# design.net
KiCad netlist of a schematic drawn in Altium Designer
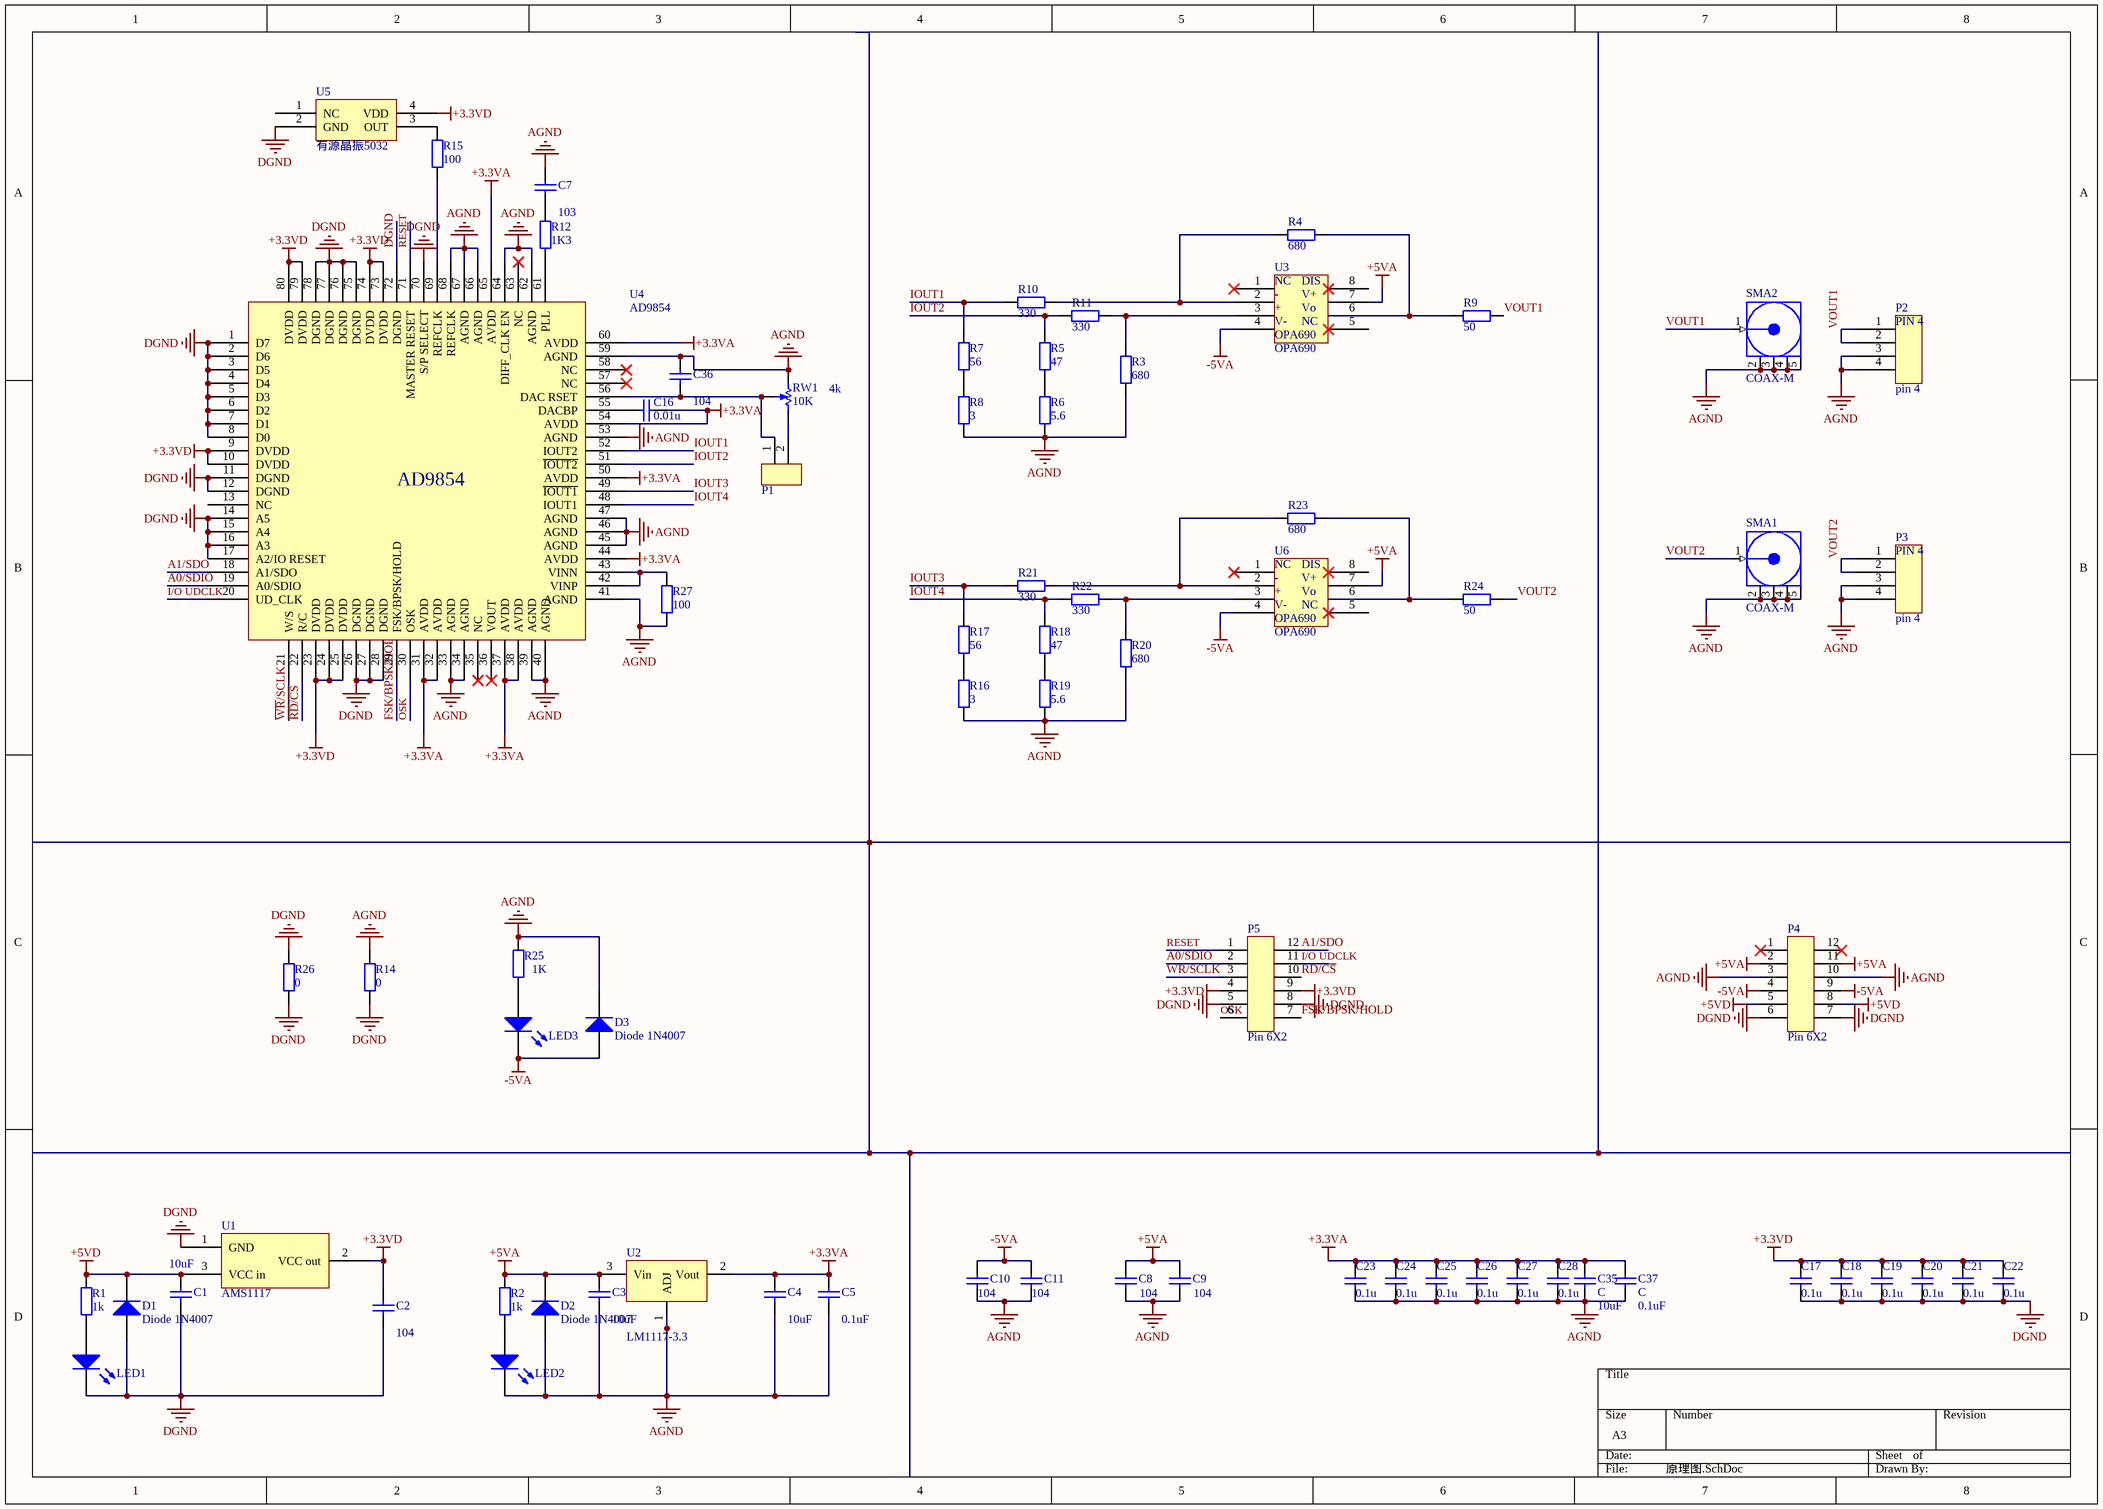
[diagram p0: 原理图.SchDoc]

(export (version "E")
  (design (tool "Eeschema 10.0.6"))
  (components
    (comp (ref "C1")
      (value "10uF")
      (footprint "0805")
      (fields (field (name "Comment") "C"))
      (libsource (lib "我的元件库") (part "C"))
    )
    (comp (ref "C2")
      (value "104")
      (footprint "0805")
      (fields (field (name "Comment") "C"))
      (libsource (lib "我的元件库") (part "C"))
    )
    (comp (ref "C3")
      (value "10uF")
      (footprint "0805")
      (fields (field (name "Comment") "C"))
      (libsource (lib "我的元件库") (part "C"))
    )
    (comp (ref "C4")
      (value "10uF")
      (footprint "0805")
      (fields (field (name "Comment") "C"))
      (libsource (lib "我的元件库") (part "C"))
    )
    (comp (ref "C5")
      (value "0.1uF")
      (footprint "0805")
      (fields (field (name "Comment") "C"))
      (libsource (lib "我的元件库") (part "C"))
    )
    (comp (ref "C7")
      (value "103")
      (footprint "0805")
      (fields (field (name "Comment") "C"))
      (libsource (lib "我的元件库") (part "C"))
    )
    (comp (ref "C8")
      (value "104")
      (footprint "0805")
      (fields (field (name "Comment") "C"))
      (libsource (lib "我的元件库") (part "C"))
    )
    (comp (ref "C9")
      (value "104")
      (footprint "0805")
      (fields (field (name "Comment") "C"))
      (libsource (lib "我的元件库") (part "C"))
    )
    (comp (ref "C10")
      (value "104")
      (footprint "0805")
      (fields (field (name "Comment") "C"))
      (libsource (lib "我的元件库") (part "C"))
    )
    (comp (ref "C11")
      (value "104")
      (footprint "0805")
      (fields (field (name "Comment") "C"))
      (libsource (lib "我的元件库") (part "C"))
    )
    (comp (ref "C16") (value "0.01u") (footprint "0805") (libsource (lib "顶层SMD") (part "C_0805")))
    (comp (ref "C17") (value "0.1u") (footprint "0805") (libsource (lib "顶层SMD") (part "C_0805")))
    (comp (ref "C18") (value "0.1u") (footprint "0805") (libsource (lib "顶层SMD") (part "C_0805")))
    (comp (ref "C19") (value "0.1u") (footprint "0805") (libsource (lib "顶层SMD") (part "C_0805")))
    (comp (ref "C20") (value "0.1u") (footprint "0805") (libsource (lib "顶层SMD") (part "C_0805")))
    (comp (ref "C21") (value "0.1u") (footprint "0805") (libsource (lib "顶层SMD") (part "C_0805")))
    (comp (ref "C22") (value "0.1u") (footprint "0805") (libsource (lib "顶层SMD") (part "C_0805")))
    (comp (ref "C23") (value "0.1u") (footprint "0805") (libsource (lib "顶层SMD") (part "C_0805")))
    (comp (ref "C24") (value "0.1u") (footprint "0805") (libsource (lib "顶层SMD") (part "C_0805")))
    (comp (ref "C25") (value "0.1u") (footprint "0805") (libsource (lib "顶层SMD") (part "C_0805")))
    (comp (ref "C26") (value "0.1u") (footprint "0805") (libsource (lib "顶层SMD") (part "C_0805")))
    (comp (ref "C27") (value "0.1u") (footprint "0805") (libsource (lib "顶层SMD") (part "C_0805")))
    (comp (ref "C28") (value "0.1u") (footprint "0805") (libsource (lib "顶层SMD") (part "C_0805")))
    (comp (ref "C35")
      (value "C")
      (footprint "0805")
      (fields (field (name "ALTIUM_VALUE") "10uF"))
      (libsource (lib "我的元件库") (part "C"))
    )
    (comp (ref "C36")
      (value "104")
      (footprint "0805")
      (fields (field (name "Comment") "C"))
      (libsource (lib "我的元件库") (part "C"))
    )
    (comp (ref "C37")
      (value "C")
      (footprint "0805")
      (fields (field (name "ALTIUM_VALUE") "0.1uF"))
      (libsource (lib "我的元件库") (part "C"))
    )
    (comp (ref "D1")
      (value "Diode 1N4007")
      (footprint "二极管SMB")
      (description "1 Amp General Purpose Rectifier")
      (fields (field (name "PUBLISHER") "Altium Limited"))
      (libsource (lib "Miscellaneous Devices") (part "Diode 1N4007"))
    )
    (comp (ref "D2")
      (value "Diode 1N4007")
      (footprint "二极管SMB")
      (description "1 Amp General Purpose Rectifier")
      (fields (field (name "PUBLISHER") "Altium Limited"))
      (libsource (lib "Miscellaneous Devices") (part "Diode 1N4007"))
    )
    (comp (ref "D3")
      (value "Diode 1N4007")
      (footprint "二极管SMB")
      (description "1 Amp General Purpose Rectifier")
      (fields (field (name "PUBLISHER") "Altium Limited"))
      (libsource (lib "Miscellaneous Devices") (part "Diode 1N4007"))
    )
    (comp (ref "LED1") (value "LED") (footprint "0805") (libsource (lib "我的元件库") (part "LED")))
    (comp (ref "LED2") (value "LED") (footprint "0805") (libsource (lib "我的元件库") (part "LED")))
    (comp (ref "LED3") (value "LED") (footprint "0805") (libsource (lib "我的元件库") (part "LED")))
    (comp (ref "P1") (value "Pin 2") (footprint "Pin 2") (libsource (lib "我的元件库") (part "Pin 2")))
    (comp (ref "P2") (value "pin 4") (footprint "pin 4") (libsource (lib "我的元件库") (part "pin 4")))
    (comp (ref "P3") (value "pin 4") (footprint "pin 4") (libsource (lib "我的元件库") (part "pin 4")))
    (comp (ref "P4") (value "Pin 6X2") (footprint "Pin 6X2") (libsource (lib "我的元件库") (part "Pin 6X2")))
    (comp (ref "P5") (value "Pin 6X2") (footprint "Pin 6X2") (libsource (lib "我的元件库") (part "Pin 6X2")))
    (comp (ref "R1")
      (value "1k")
      (footprint "0805")
      (fields (field (name "Comment") "R"))
      (libsource (lib "我的元件库") (part "R"))
    )
    (comp (ref "R2")
      (value "1k")
      (footprint "0805")
      (fields (field (name "Comment") "R"))
      (libsource (lib "我的元件库") (part "R"))
    )
    (comp (ref "R3")
      (value "680")
      (footprint "0805")
      (fields (field (name "Comment") "R"))
      (libsource (lib "我的元件库") (part "R"))
    )
    (comp (ref "R4")
      (value "680")
      (footprint "0805")
      (fields (field (name "Comment") "R"))
      (libsource (lib "") (part "R_1"))
    )
    (comp (ref "R5")
      (value "47")
      (footprint "0805")
      (fields (field (name "Comment") "R"))
      (libsource (lib "我的元件库") (part "R"))
    )
    (comp (ref "R6")
      (value "5.6")
      (footprint "0805")
      (fields (field (name "Comment") "R"))
      (libsource (lib "我的元件库") (part "R"))
    )
    (comp (ref "R7")
      (value "56")
      (footprint "0805")
      (fields (field (name "Comment") "R"))
      (libsource (lib "我的元件库") (part "R"))
    )
    (comp (ref "R8")
      (value "3")
      (footprint "0805")
      (fields (field (name "Comment") "R"))
      (libsource (lib "我的元件库") (part "R"))
    )
    (comp (ref "R9")
      (value "50")
      (footprint "0805")
      (fields (field (name "Comment") "R"))
      (libsource (lib "") (part "R_1"))
    )
    (comp (ref "R10")
      (value "330")
      (footprint "0805")
      (fields (field (name "Comment") "R"))
      (libsource (lib "") (part "R_1"))
    )
    (comp (ref "R11")
      (value "330")
      (footprint "0805")
      (fields (field (name "Comment") "R"))
      (libsource (lib "") (part "R_1"))
    )
    (comp (ref "R12") (value "1K3") (footprint "0805") (libsource (lib "顶层SMD") (part "R_0805")))
    (comp (ref "R14") (value "0") (footprint "0805") (libsource (lib "顶层SMD") (part "R_0805")))
    (comp (ref "R15")
      (value "100")
      (footprint "0805")
      (fields (field (name "Comment") "R"))
      (libsource (lib "我的元件库") (part "R"))
    )
    (comp (ref "R16")
      (value "3")
      (footprint "0805")
      (fields (field (name "Comment") "R"))
      (libsource (lib "我的元件库") (part "R"))
    )
    (comp (ref "R17")
      (value "56")
      (footprint "0805")
      (fields (field (name "Comment") "R"))
      (libsource (lib "我的元件库") (part "R"))
    )
    (comp (ref "R18")
      (value "47")
      (footprint "0805")
      (fields (field (name "Comment") "R"))
      (libsource (lib "我的元件库") (part "R"))
    )
    (comp (ref "R19")
      (value "5.6")
      (footprint "0805")
      (fields (field (name "Comment") "R"))
      (libsource (lib "我的元件库") (part "R"))
    )
    (comp (ref "R20")
      (value "680")
      (footprint "0805")
      (fields (field (name "Comment") "R"))
      (libsource (lib "我的元件库") (part "R"))
    )
    (comp (ref "R21")
      (value "330")
      (footprint "0805")
      (fields (field (name "Comment") "R"))
      (libsource (lib "") (part "R_1"))
    )
    (comp (ref "R22")
      (value "330")
      (footprint "0805")
      (fields (field (name "Comment") "R"))
      (libsource (lib "") (part "R_1"))
    )
    (comp (ref "R23")
      (value "680")
      (footprint "0805")
      (fields (field (name "Comment") "R"))
      (libsource (lib "") (part "R_1"))
    )
    (comp (ref "R24")
      (value "50")
      (footprint "0805")
      (fields (field (name "Comment") "R"))
      (libsource (lib "") (part "R_1"))
    )
    (comp (ref "R25")
      (value "1K")
      (footprint "0805")
      (fields (field (name "Comment") "R"))
      (libsource (lib "我的元件库") (part "R"))
    )
    (comp (ref "R26") (value "0") (footprint "0805") (libsource (lib "顶层SMD") (part "R_0805")))
    (comp (ref "R27")
      (value "100")
      (footprint "0805")
      (fields (field (name "Comment") "R"))
      (libsource (lib "") (part "R_2"))
    )
    (comp (ref "RW1")
      (value "10K")
      (footprint "电位器")
      (fields (field (name "Comment") "R"))
      (libsource (lib "我的元件库") (part "电位器"))
    )
    (comp (ref "SMA1")
      (value "COAX-M")
      (footprint "SMB_V-RJ45")
      (description "RF Coaxial PCB Connector, MMCX; Thru-Hole, Vertical Mount Plug,  50 Ohm Impedance")
      (fields (field (name "PUBLISHER") "Altium Limited"))
      (libsource (lib "Miscellaneous Connectors") (part "COAX-M"))
    )
    (comp (ref "SMA2")
      (value "COAX-M")
      (footprint "SMB_V-RJ45")
      (description "RF Coaxial PCB Connector, MMCX; Thru-Hole, Vertical Mount Plug,  50 Ohm Impedance")
      (fields (field (name "PUBLISHER") "Altium Limited"))
      (libsource (lib "Miscellaneous Connectors") (part "COAX-M"))
    )
    (comp (ref "U1") (value "AMS1117") (footprint "AMS1117") (libsource (lib "我的元件库") (part "AMS1117")))
    (comp (ref "U2") (value "LM1117-3.3") (footprint "LM78**") (libsource (lib "我的元件库") (part "LM317")))
    (comp (ref "U3") (value "OPA690") (footprint "SOP-8") (libsource (lib "我的元件库") (part "OPA690")))
    (comp (ref "U4") (value "AD9854") (footprint "LPQF 80 9854") (libsource (lib "我的集成库") (part "AD9854")))
    (comp (ref "U5") (value "有源晶振5032") (footprint "7050晶振") (libsource (lib "我的集成库") (part "有源晶振5032")))
    (comp (ref "U6") (value "OPA690") (footprint "SOP-8") (libsource (lib "我的元件库") (part "OPA690")))
  )
  (nets
    (net (code "1") (name "+3.3VA") (class "Default")
      (node (ref "C16") (pin "1") (pinfunction "1_1") (pintype "passive"))
      (node (ref "C23") (pin "2") (pinfunction "2_2") (pintype "passive"))
      (node (ref "C24") (pin "2") (pinfunction "2_2") (pintype "passive"))
      (node (ref "C25") (pin "2") (pinfunction "2_2") (pintype "passive"))
      (node (ref "C26") (pin "2") (pinfunction "2_2") (pintype "passive"))
      (node (ref "C27") (pin "2") (pinfunction "2_2") (pintype "passive"))
      (node (ref "C28") (pin "2") (pinfunction "2_2") (pintype "passive"))
      (node (ref "C35") (pin "2") (pinfunction "2_2") (pintype "passive"))
      (node (ref "C37") (pin "2") (pinfunction "2_2") (pintype "passive"))
      (node (ref "C4") (pin "2") (pinfunction "2_2") (pintype "passive"))
      (node (ref "C5") (pin "2") (pinfunction "2_2") (pintype "passive"))
      (node (ref "U2") (pin "2") (pinfunction "Vout_2") (pintype "passive"))
      (node (ref "U4") (pin "31") (pinfunction "AVDD_31") (pintype "passive"))
      (node (ref "U4") (pin "32") (pinfunction "AVDD_32") (pintype "passive"))
      (node (ref "U4") (pin "37") (pinfunction "AVDD_37") (pintype "passive"))
      (node (ref "U4") (pin "38") (pinfunction "AVDD_38") (pintype "passive"))
      (node (ref "U4") (pin "44") (pinfunction "AVDD_44") (pintype "passive"))
      (node (ref "U4") (pin "50") (pinfunction "AVDD_50") (pintype "passive"))
      (node (ref "U4") (pin "54") (pinfunction "AVDD_54") (pintype "passive"))
      (node (ref "U4") (pin "60") (pinfunction "AVDD_60") (pintype "passive"))
      (node (ref "U4") (pin "65") (pinfunction "AVDD_65") (pintype "passive"))
    )
    (net (code "2") (name "+3.3VD") (class "Default")
      (node (ref "C17") (pin "2") (pinfunction "2_2") (pintype "passive"))
      (node (ref "C18") (pin "2") (pinfunction "2_2") (pintype "passive"))
      (node (ref "C19") (pin "2") (pinfunction "2_2") (pintype "passive"))
      (node (ref "C2") (pin "2") (pinfunction "2_2") (pintype "passive"))
      (node (ref "C20") (pin "2") (pinfunction "2_2") (pintype "passive"))
      (node (ref "C21") (pin "2") (pinfunction "2_2") (pintype "passive"))
      (node (ref "C22") (pin "2") (pinfunction "2_2") (pintype "passive"))
      (node (ref "P5") (pin "4") (pinfunction "4_4") (pintype "passive"))
      (node (ref "P5") (pin "9") (pinfunction "9_9") (pintype "passive"))
      (node (ref "U1") (pin "2") (pinfunction "VCC_out_2") (pintype "power_in"))
      (node (ref "U4") (pin "10") (pinfunction "DVDD_10") (pintype "passive"))
      (node (ref "U4") (pin "23") (pinfunction "DVDD_23") (pintype "passive"))
      (node (ref "U4") (pin "24") (pinfunction "DVDD_24") (pintype "passive"))
      (node (ref "U4") (pin "25") (pinfunction "DVDD_25") (pintype "passive"))
      (node (ref "U4") (pin "73") (pinfunction "DVDD_73") (pintype "passive"))
      (node (ref "U4") (pin "74") (pinfunction "DVDD_74") (pintype "passive"))
      (node (ref "U4") (pin "79") (pinfunction "DVDD_79") (pintype "passive"))
      (node (ref "U4") (pin "80") (pinfunction "DVDD_80") (pintype "passive"))
      (node (ref "U4") (pin "9") (pinfunction "DVDD_9") (pintype "passive"))
      (node (ref "U5") (pin "4") (pinfunction "VDD_4") (pintype "passive"))
    )
    (net (code "3") (name "+5VA") (class "Default")
      (node (ref "C3") (pin "2") (pinfunction "2_2") (pintype "passive"))
      (node (ref "C8") (pin "2") (pinfunction "2_2") (pintype "passive"))
      (node (ref "C9") (pin "2") (pinfunction "2_2") (pintype "passive"))
      (node (ref "D2") (pin "2") (pinfunction "K_2") (pintype "passive"))
      (node (ref "P4") (pin "11") (pinfunction "11_11") (pintype "passive"))
      (node (ref "P4") (pin "2") (pinfunction "2_2") (pintype "passive"))
      (node (ref "R2") (pin "2") (pinfunction "2_2") (pintype "passive"))
      (node (ref "U2") (pin "3") (pinfunction "Vin_3") (pintype "passive"))
      (node (ref "U3") (pin "7") (pintype "passive"))
      (node (ref "U6") (pin "7") (pintype "passive"))
    )
    (net (code "4") (name "+5VD") (class "Default")
      (node (ref "C1") (pin "1") (pinfunction "1_1") (pintype "passive"))
      (node (ref "D1") (pin "2") (pinfunction "K_2") (pintype "passive"))
      (node (ref "P4") (pin "5") (pinfunction "5_5") (pintype "passive"))
      (node (ref "P4") (pin "8") (pinfunction "8_8") (pintype "passive"))
      (node (ref "R1") (pin "2") (pinfunction "2_2") (pintype "passive"))
      (node (ref "U1") (pin "3") (pinfunction "VCC_in_3") (pintype "power_in"))
    )
    (net (code "5") (name "-5VA") (class "Default")
      (node (ref "C10") (pin "2") (pinfunction "2_2") (pintype "passive"))
      (node (ref "C11") (pin "2") (pinfunction "2_2") (pintype "passive"))
      (node (ref "D3") (pin "1") (pinfunction "A_1") (pintype "passive"))
      (node (ref "LED3") (pin "2") (pinfunction "K_2") (pintype "passive"))
      (node (ref "P4") (pin "4") (pinfunction "4_4") (pintype "passive"))
      (node (ref "P4") (pin "9") (pinfunction "9_9") (pintype "passive"))
      (node (ref "U3") (pin "4") (pintype "passive"))
      (node (ref "U6") (pin "4") (pintype "passive"))
    )
    (net (code "6") (name "/A0{slash}SDIO") (class "Default")
      (node (ref "P5") (pin "2") (pinfunction "2_2") (pintype "passive"))
      (node (ref "U4") (pin "19") (pinfunction "A0/SDIO_19") (pintype "passive"))
    )
    (net (code "7") (name "/A1{slash}SDO") (class "Default")
      (node (ref "P5") (pin "12") (pinfunction "12_12") (pintype "passive"))
      (node (ref "U4") (pin "18") (pinfunction "A1/SDO_18") (pintype "passive"))
    )
    (net (code "8") (name "/FSK{slash}BPSK{slash}HOLD") (class "Default")
      (node (ref "P5") (pin "7") (pinfunction "7_7") (pintype "passive"))
      (node (ref "U4") (pin "29") (pinfunction "FSK/BPSK/HOLD_29") (pintype "passive"))
    )
    (net (code "9") (name "/IOUT1") (class "Default")
      (node (ref "R10") (pin "1") (pinfunction "1_1") (pintype "passive"))
      (node (ref "R7") (pin "2") (pinfunction "2_2") (pintype "passive"))
      (node (ref "U4") (pin "52") (pinfunction "IOUT2_52") (pintype "passive"))
    )
    (net (code "10") (name "/IOUT2") (class "Default")
      (node (ref "R11") (pin "1") (pinfunction "1_1") (pintype "passive"))
      (node (ref "R5") (pin "2") (pinfunction "2_2") (pintype "passive"))
      (node (ref "U4") (pin "51") (pinfunction "~{IOUT2}_51") (pintype "passive"))
    )
    (net (code "11") (name "/IOUT3") (class "Default")
      (node (ref "R17") (pin "2") (pinfunction "2_2") (pintype "passive"))
      (node (ref "R21") (pin "1") (pinfunction "1_1") (pintype "passive"))
      (node (ref "U4") (pin "49") (pinfunction "~{IOUT1}_49") (pintype "passive"))
    )
    (net (code "12") (name "/IOUT4") (class "Default")
      (node (ref "R18") (pin "2") (pinfunction "2_2") (pintype "passive"))
      (node (ref "R22") (pin "1") (pinfunction "1_1") (pintype "passive"))
      (node (ref "U4") (pin "48") (pinfunction "IOUT1_48") (pintype "passive"))
    )
    (net (code "13") (name "/I{slash}O UDCLK") (class "Default")
      (node (ref "P5") (pin "11") (pinfunction "11_11") (pintype "passive"))
      (node (ref "U4") (pin "20") (pinfunction "UD_CLK_20") (pintype "passive"))
    )
    (net (code "14") (name "/OSK") (class "Default")
      (node (ref "P5") (pin "6") (pinfunction "6_6") (pintype "passive"))
      (node (ref "U4") (pin "30") (pinfunction "OSK_30") (pintype "passive"))
    )
    (net (code "15") (name "/RESET") (class "Default")
      (node (ref "P5") (pin "1") (pinfunction "1_1") (pintype "passive"))
      (node (ref "U4") (pin "71") (pinfunction "MASTER_RESET_71") (pintype "passive"))
    )
    (net (code "16") (name "/VOUT1") (class "Default")
      (node (ref "P2") (pin "1") (pintype "passive"))
      (node (ref "P2") (pin "2") (pintype "passive"))
      (node (ref "R9") (pin "2") (pinfunction "2_2") (pintype "passive"))
      (node (ref "SMA2") (pin "1") (pinfunction "Signal_1") (pintype "input"))
    )
    (net (code "17") (name "/VOUT2") (class "Default")
      (node (ref "P3") (pin "1") (pintype "passive"))
      (node (ref "P3") (pin "2") (pintype "passive"))
      (node (ref "R24") (pin "2") (pinfunction "2_2") (pintype "passive"))
      (node (ref "SMA1") (pin "1") (pinfunction "Signal_1") (pintype "input"))
    )
    (net (code "18") (name "/~{RD}{slash}~{CS}") (class "Default")
      (node (ref "P5") (pin "10") (pinfunction "10_10") (pintype "passive"))
      (node (ref "U4") (pin "22") (pinfunction "R/C_22") (pintype "passive"))
    )
    (net (code "19") (name "/~{WR}{slash}SCLK") (class "Default")
      (node (ref "P5") (pin "3") (pinfunction "3_3") (pintype "passive"))
      (node (ref "U4") (pin "21") (pinfunction "W/S_21") (pintype "passive"))
    )
    (net (code "20") (name "AGND") (class "Default")
      (node (ref "C10") (pin "1") (pinfunction "1_1") (pintype "passive"))
      (node (ref "C11") (pin "1") (pinfunction "1_1") (pintype "passive"))
      (node (ref "C23") (pin "1") (pinfunction "1_1") (pintype "passive"))
      (node (ref "C24") (pin "1") (pinfunction "1_1") (pintype "passive"))
      (node (ref "C25") (pin "1") (pinfunction "1_1") (pintype "passive"))
      (node (ref "C26") (pin "1") (pinfunction "1_1") (pintype "passive"))
      (node (ref "C27") (pin "1") (pinfunction "1_1") (pintype "passive"))
      (node (ref "C28") (pin "1") (pinfunction "1_1") (pintype "passive"))
      (node (ref "C3") (pin "1") (pinfunction "1_1") (pintype "passive"))
      (node (ref "C35") (pin "1") (pinfunction "1_1") (pintype "passive"))
      (node (ref "C36") (pin "2") (pinfunction "2_2") (pintype "passive"))
      (node (ref "C37") (pin "1") (pinfunction "1_1") (pintype "passive"))
      (node (ref "C4") (pin "1") (pinfunction "1_1") (pintype "passive"))
      (node (ref "C5") (pin "1") (pinfunction "1_1") (pintype "passive"))
      (node (ref "C7") (pin "2") (pinfunction "2_2") (pintype "passive"))
      (node (ref "C8") (pin "1") (pinfunction "1_1") (pintype "passive"))
      (node (ref "C9") (pin "1") (pinfunction "1_1") (pintype "passive"))
      (node (ref "D2") (pin "1") (pinfunction "A_1") (pintype "passive"))
      (node (ref "D3") (pin "2") (pinfunction "K_2") (pintype "passive"))
      (node (ref "LED2") (pin "2") (pinfunction "K_2") (pintype "passive"))
      (node (ref "P2") (pin "3") (pintype "passive"))
      (node (ref "P2") (pin "4") (pintype "passive"))
      (node (ref "P3") (pin "3") (pintype "passive"))
      (node (ref "P3") (pin "4") (pintype "passive"))
      (node (ref "P4") (pin "10") (pinfunction "10_10") (pintype "passive"))
      (node (ref "P4") (pin "3") (pinfunction "3_3") (pintype "passive"))
      (node (ref "R14") (pin "2") (pinfunction "2_2") (pintype "passive"))
      (node (ref "R16") (pin "1") (pinfunction "1_1") (pintype "passive"))
      (node (ref "R19") (pin "1") (pinfunction "1_1") (pintype "passive"))
      (node (ref "R20") (pin "1") (pinfunction "1_1") (pintype "passive"))
      (node (ref "R25") (pin "2") (pinfunction "2_2") (pintype "passive"))
      (node (ref "R27") (pin "2") (pinfunction "2_2") (pintype "passive"))
      (node (ref "R3") (pin "1") (pinfunction "1_1") (pintype "passive"))
      (node (ref "R6") (pin "1") (pinfunction "1_1") (pintype "passive"))
      (node (ref "R8") (pin "1") (pinfunction "1_1") (pintype "passive"))
      (node (ref "RW1") (pin "3") (pinfunction "-_3") (pintype "passive"))
      (node (ref "SMA1") (pin "2") (pinfunction "GND_2") (pintype "power_in"))
      (node (ref "SMA1") (pin "3") (pinfunction "GND_3") (pintype "power_in"))
      (node (ref "SMA1") (pin "4") (pinfunction "GND_4") (pintype "power_in"))
      (node (ref "SMA1") (pin "5") (pinfunction "GND_5") (pintype "power_in"))
      (node (ref "SMA2") (pin "2") (pinfunction "GND_2") (pintype "power_in"))
      (node (ref "SMA2") (pin "3") (pinfunction "GND_3") (pintype "power_in"))
      (node (ref "SMA2") (pin "4") (pinfunction "GND_4") (pintype "power_in"))
      (node (ref "SMA2") (pin "5") (pinfunction "GND_5") (pintype "power_in"))
      (node (ref "U2") (pin "1") (pinfunction "ADJ_1") (pintype "passive"))
      (node (ref "U4") (pin "33") (pinfunction "AGND_33") (pintype "passive"))
      (node (ref "U4") (pin "34") (pinfunction "AGND_34") (pintype "passive"))
      (node (ref "U4") (pin "39") (pinfunction "AGND_39") (pintype "passive"))
      (node (ref "U4") (pin "40") (pinfunction "AGND_40") (pintype "passive"))
      (node (ref "U4") (pin "41") (pinfunction "AGND_41") (pintype "passive"))
      (node (ref "U4") (pin "45") (pinfunction "AGND_45") (pintype "passive"))
      (node (ref "U4") (pin "46") (pinfunction "AGND_46") (pintype "passive"))
      (node (ref "U4") (pin "47") (pinfunction "AGND_47") (pintype "passive"))
      (node (ref "U4") (pin "53") (pinfunction "AGND_53") (pintype "passive"))
      (node (ref "U4") (pin "59") (pinfunction "AGND_59") (pintype "passive"))
      (node (ref "U4") (pin "62") (pinfunction "AGND_62") (pintype "passive"))
      (node (ref "U4") (pin "64") (pinfunction "DIFF_CLK_EN_64") (pintype "passive"))
      (node (ref "U4") (pin "66") (pinfunction "AGND_66") (pintype "passive"))
      (node (ref "U4") (pin "67") (pinfunction "AGND_67") (pintype "passive"))
      (node (ref "U4") (pin "68") (pinfunction "REFCLK_68") (pintype "passive"))
    )
    (net (code "21") (name "DGND") (class "Default")
      (node (ref "C1") (pin "2") (pinfunction "2_2") (pintype "passive"))
      (node (ref "C17") (pin "1") (pinfunction "1_1") (pintype "passive"))
      (node (ref "C18") (pin "1") (pinfunction "1_1") (pintype "passive"))
      (node (ref "C19") (pin "1") (pinfunction "1_1") (pintype "passive"))
      (node (ref "C2") (pin "1") (pinfunction "1_1") (pintype "passive"))
      (node (ref "C20") (pin "1") (pinfunction "1_1") (pintype "passive"))
      (node (ref "C21") (pin "1") (pinfunction "1_1") (pintype "passive"))
      (node (ref "C22") (pin "1") (pinfunction "1_1") (pintype "passive"))
      (node (ref "D1") (pin "1") (pinfunction "A_1") (pintype "passive"))
      (node (ref "LED1") (pin "2") (pinfunction "K_2") (pintype "passive"))
      (node (ref "P4") (pin "6") (pinfunction "6_6") (pintype "passive"))
      (node (ref "P4") (pin "7") (pinfunction "7_7") (pintype "passive"))
      (node (ref "P5") (pin "5") (pinfunction "5_5") (pintype "passive"))
      (node (ref "P5") (pin "8") (pinfunction "8_8") (pintype "passive"))
      (node (ref "R14") (pin "1") (pinfunction "1_1") (pintype "passive"))
      (node (ref "R26") (pin "1") (pinfunction "1_1") (pintype "passive"))
      (node (ref "R26") (pin "2") (pinfunction "2_2") (pintype "passive"))
      (node (ref "U1") (pin "1") (pinfunction "GND_1") (pintype "power_in"))
      (node (ref "U4") (pin "1") (pinfunction "D7_1") (pintype "passive"))
      (node (ref "U4") (pin "11") (pinfunction "DGND_11") (pintype "passive"))
      (node (ref "U4") (pin "12") (pinfunction "DGND_12") (pintype "passive"))
      (node (ref "U4") (pin "14") (pinfunction "A5_14") (pintype "passive"))
      (node (ref "U4") (pin "15") (pinfunction "A4_15") (pintype "passive"))
      (node (ref "U4") (pin "16") (pinfunction "A3_16") (pintype "passive"))
      (node (ref "U4") (pin "17") (pinfunction "A2/IO_RESET_17") (pintype "passive"))
      (node (ref "U4") (pin "2") (pinfunction "D6_2") (pintype "passive"))
      (node (ref "U4") (pin "26") (pinfunction "DGND_26") (pintype "passive"))
      (node (ref "U4") (pin "27") (pinfunction "DGND_27") (pintype "passive"))
      (node (ref "U4") (pin "28") (pinfunction "DGND_28") (pintype "passive"))
      (node (ref "U4") (pin "3") (pinfunction "D5_3") (pintype "passive"))
      (node (ref "U4") (pin "4") (pinfunction "D4_4") (pintype "passive"))
      (node (ref "U4") (pin "5") (pinfunction "D3_5") (pintype "passive"))
      (node (ref "U4") (pin "6") (pinfunction "D2_6") (pintype "passive"))
      (node (ref "U4") (pin "7") (pinfunction "D1_7") (pintype "passive"))
      (node (ref "U4") (pin "70") (pinfunction "S/P_SELECT_70") (pintype "passive"))
      (node (ref "U4") (pin "72") (pinfunction "DGND_72") (pintype "passive"))
      (node (ref "U4") (pin "75") (pinfunction "DGND_75") (pintype "passive"))
      (node (ref "U4") (pin "76") (pinfunction "DGND_76") (pintype "passive"))
      (node (ref "U4") (pin "77") (pinfunction "DGND_77") (pintype "passive"))
      (node (ref "U4") (pin "78") (pinfunction "DGND_78") (pintype "passive"))
      (node (ref "U4") (pin "8") (pinfunction "D0_8") (pintype "passive"))
      (node (ref "U5") (pin "2") (pinfunction "GND_2") (pintype "passive"))
    )
    (net (code "22") (name "Net-(C7-Pad1)") (class "Default")
      (node (ref "C7") (pin "1") (pinfunction "1_1") (pintype "passive"))
      (node (ref "R12") (pin "2") (pinfunction "2_2") (pintype "passive"))
    )
    (net (code "23") (name "Net-(LED1-A)") (class "Default")
      (node (ref "LED1") (pin "1") (pinfunction "A_1") (pintype "passive"))
      (node (ref "R1") (pin "1") (pinfunction "1_1") (pintype "passive"))
    )
    (net (code "24") (name "Net-(LED2-A)") (class "Default")
      (node (ref "LED2") (pin "1") (pinfunction "A_1") (pintype "passive"))
      (node (ref "R2") (pin "1") (pinfunction "1_1") (pintype "passive"))
    )
    (net (code "25") (name "Net-(LED3-A)") (class "Default")
      (node (ref "LED3") (pin "1") (pinfunction "A_1") (pintype "passive"))
      (node (ref "R25") (pin "1") (pinfunction "1_1") (pintype "passive"))
    )
    (net (code "26") (name "Net-(R4-Pad2)") (class "Default")
      (node (ref "R4") (pin "2") (pinfunction "2_2") (pintype "passive"))
      (node (ref "R9") (pin "1") (pinfunction "1_1") (pintype "passive"))
      (node (ref "U3") (pin "6") (pintype "passive"))
    )
    (net (code "27") (name "Net-(R5-Pad1)") (class "Default")
      (node (ref "R5") (pin "1") (pinfunction "1_1") (pintype "passive"))
      (node (ref "R6") (pin "2") (pinfunction "2_2") (pintype "passive"))
    )
    (net (code "28") (name "Net-(R7-Pad1)") (class "Default")
      (node (ref "R7") (pin "1") (pinfunction "1_1") (pintype "passive"))
      (node (ref "R8") (pin "2") (pinfunction "2_2") (pintype "passive"))
    )
    (net (code "29") (name "Net-(R10-Pad2)") (class "Default")
      (node (ref "R10") (pin "2") (pinfunction "2_2") (pintype "passive"))
      (node (ref "R4") (pin "1") (pinfunction "1_1") (pintype "passive"))
      (node (ref "U3") (pin "2") (pintype "passive"))
    )
    (net (code "30") (name "Net-(R11-Pad2)") (class "Default")
      (node (ref "R11") (pin "2") (pinfunction "2_2") (pintype "passive"))
      (node (ref "R3") (pin "2") (pinfunction "2_2") (pintype "passive"))
      (node (ref "U3") (pin "3") (pintype "passive"))
    )
    (net (code "31") (name "Net-(R15-Pad1)") (class "Default")
      (node (ref "R15") (pin "1") (pinfunction "1_1") (pintype "passive"))
      (node (ref "U4") (pin "69") (pinfunction "REFCLK_69") (pintype "passive"))
    )
    (net (code "32") (name "Net-(R16-Pad2)") (class "Default")
      (node (ref "R16") (pin "2") (pinfunction "2_2") (pintype "passive"))
      (node (ref "R17") (pin "1") (pinfunction "1_1") (pintype "passive"))
    )
    (net (code "33") (name "Net-(R18-Pad1)") (class "Default")
      (node (ref "R18") (pin "1") (pinfunction "1_1") (pintype "passive"))
      (node (ref "R19") (pin "2") (pinfunction "2_2") (pintype "passive"))
    )
    (net (code "34") (name "Net-(R20-Pad2)") (class "Default")
      (node (ref "R20") (pin "2") (pinfunction "2_2") (pintype "passive"))
      (node (ref "R22") (pin "2") (pinfunction "2_2") (pintype "passive"))
      (node (ref "U6") (pin "3") (pintype "passive"))
    )
    (net (code "35") (name "Net-(R21-Pad2)") (class "Default")
      (node (ref "R21") (pin "2") (pinfunction "2_2") (pintype "passive"))
      (node (ref "R23") (pin "1") (pinfunction "1_1") (pintype "passive"))
      (node (ref "U6") (pin "2") (pintype "passive"))
    )
    (net (code "36") (name "Net-(R23-Pad2)") (class "Default")
      (node (ref "R23") (pin "2") (pinfunction "2_2") (pintype "passive"))
      (node (ref "R24") (pin "1") (pinfunction "1_1") (pintype "passive"))
      (node (ref "U6") (pin "6") (pintype "passive"))
    )
    (net (code "37") (name "Net-(RW1-+)") (class "Default")
      (node (ref "P1") (pin "2") (pintype "passive"))
      (node (ref "RW1") (pin "1") (pinfunction "+_1") (pintype "passive"))
    )
    (net (code "38") (name "Net-(RW1-W)") (class "Default")
      (node (ref "C36") (pin "1") (pinfunction "1_1") (pintype "passive"))
      (node (ref "P1") (pin "1") (pintype "passive"))
      (node (ref "RW1") (pin "2") (pinfunction "W_2") (pintype "passive"))
      (node (ref "U4") (pin "56") (pinfunction "DAC_RSET_56") (pintype "passive"))
    )
    (net (code "39") (name "Net-(U4-DACBP)") (class "Default")
      (node (ref "C16") (pin "2") (pinfunction "2_2") (pintype "passive"))
      (node (ref "U4") (pin "55") (pinfunction "DACBP_55") (pintype "passive"))
    )
    (net (code "40") (name "Net-(U4-PLL)") (class "Default")
      (node (ref "R12") (pin "1") (pinfunction "1_1") (pintype "passive"))
      (node (ref "U4") (pin "61") (pinfunction "PLL_61") (pintype "passive"))
    )
    (net (code "41") (name "Net-(U4-VINN)") (class "Default")
      (node (ref "R27") (pin "1") (pinfunction "1_1") (pintype "passive"))
      (node (ref "U4") (pin "42") (pinfunction "VINP_42") (pintype "passive"))
      (node (ref "U4") (pin "43") (pinfunction "VINN_43") (pintype "passive"))
    )
    (net (code "42") (name "Net-(U5-OUT)") (class "Default")
      (node (ref "R15") (pin "2") (pinfunction "2_2") (pintype "passive"))
      (node (ref "U5") (pin "3") (pinfunction "OUT_3") (pintype "passive"))
    )
    (net (code "43") (name "unconnected-(P4-Pad1)") (class "Default")
      (node (ref "P4") (pin "1") (pinfunction "1_1") (pintype "passive+no_connect"))
    )
    (net (code "44") (name "unconnected-(P4-Pad12)") (class "Default")
      (node (ref "P4") (pin "12") (pinfunction "12_12") (pintype "passive+no_connect"))
    )
    (net (code "45") (name "unconnected-(U3-Pad1)") (class "Default")
      (node (ref "U3") (pin "1") (pintype "passive+no_connect"))
    )
    (net (code "46") (name "unconnected-(U3-Pad5)") (class "Default")
      (node (ref "U3") (pin "5") (pintype "passive+no_connect"))
    )
    (net (code "47") (name "unconnected-(U3-Pad8)") (class "Default")
      (node (ref "U3") (pin "8") (pintype "passive+no_connect"))
    )
    (net (code "48") (name "unconnected-(U4-NC-Pad13)") (class "Default")
      (node (ref "U4") (pin "13") (pinfunction "NC_13") (pintype "passive"))
    )
    (net (code "49") (name "unconnected-(U4-NC-Pad35)") (class "Default")
      (node (ref "U4") (pin "35") (pinfunction "NC_35") (pintype "passive+no_connect"))
    )
    (net (code "50") (name "unconnected-(U4-NC-Pad57)") (class "Default")
      (node (ref "U4") (pin "57") (pinfunction "NC_57") (pintype "passive+no_connect"))
    )
    (net (code "51") (name "unconnected-(U4-NC-Pad58)") (class "Default")
      (node (ref "U4") (pin "58") (pinfunction "NC_58") (pintype "passive+no_connect"))
    )
    (net (code "52") (name "unconnected-(U4-NC-Pad63)") (class "Default")
      (node (ref "U4") (pin "63") (pinfunction "NC_63") (pintype "passive+no_connect"))
    )
    (net (code "53") (name "unconnected-(U4-VOUT-Pad36)") (class "Default")
      (node (ref "U4") (pin "36") (pinfunction "VOUT_36") (pintype "passive+no_connect"))
    )
    (net (code "54") (name "unconnected-(U5-NC-Pad1)") (class "Default")
      (node (ref "U5") (pin "1") (pinfunction "NC_1") (pintype "passive"))
    )
    (net (code "55") (name "unconnected-(U6-Pad1)") (class "Default")
      (node (ref "U6") (pin "1") (pintype "passive+no_connect"))
    )
    (net (code "56") (name "unconnected-(U6-Pad5)") (class "Default")
      (node (ref "U6") (pin "5") (pintype "passive+no_connect"))
    )
    (net (code "57") (name "unconnected-(U6-Pad8)") (class "Default")
      (node (ref "U6") (pin "8") (pintype "passive+no_connect"))
    )
  )
)
